# SparkFun_RTK_Express.net
KiCad netlist of a schematic drawn in EAGLE
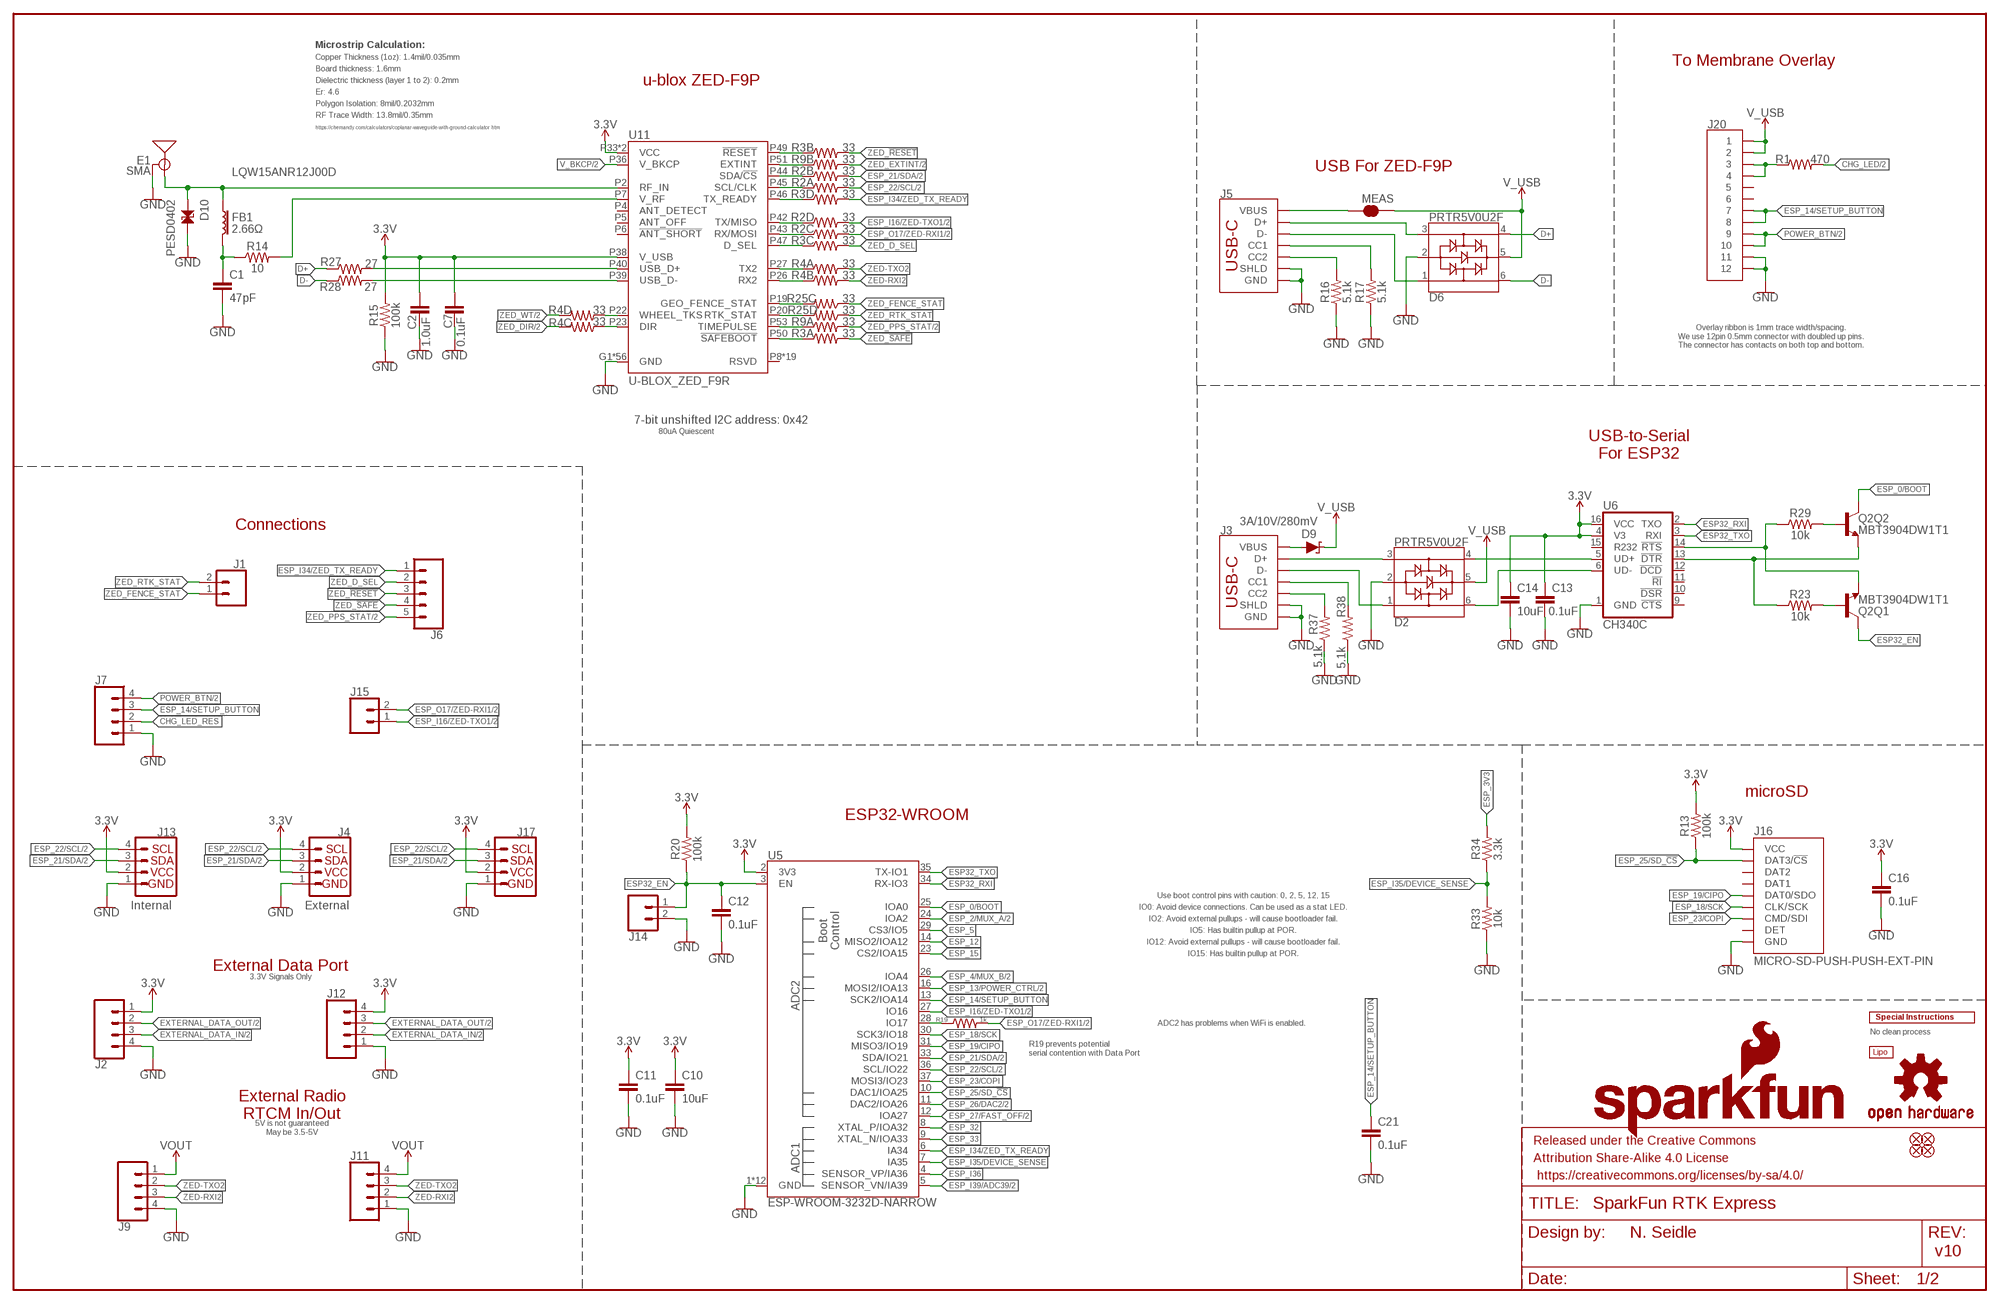
[diagram p0: schematic, sheet 1]
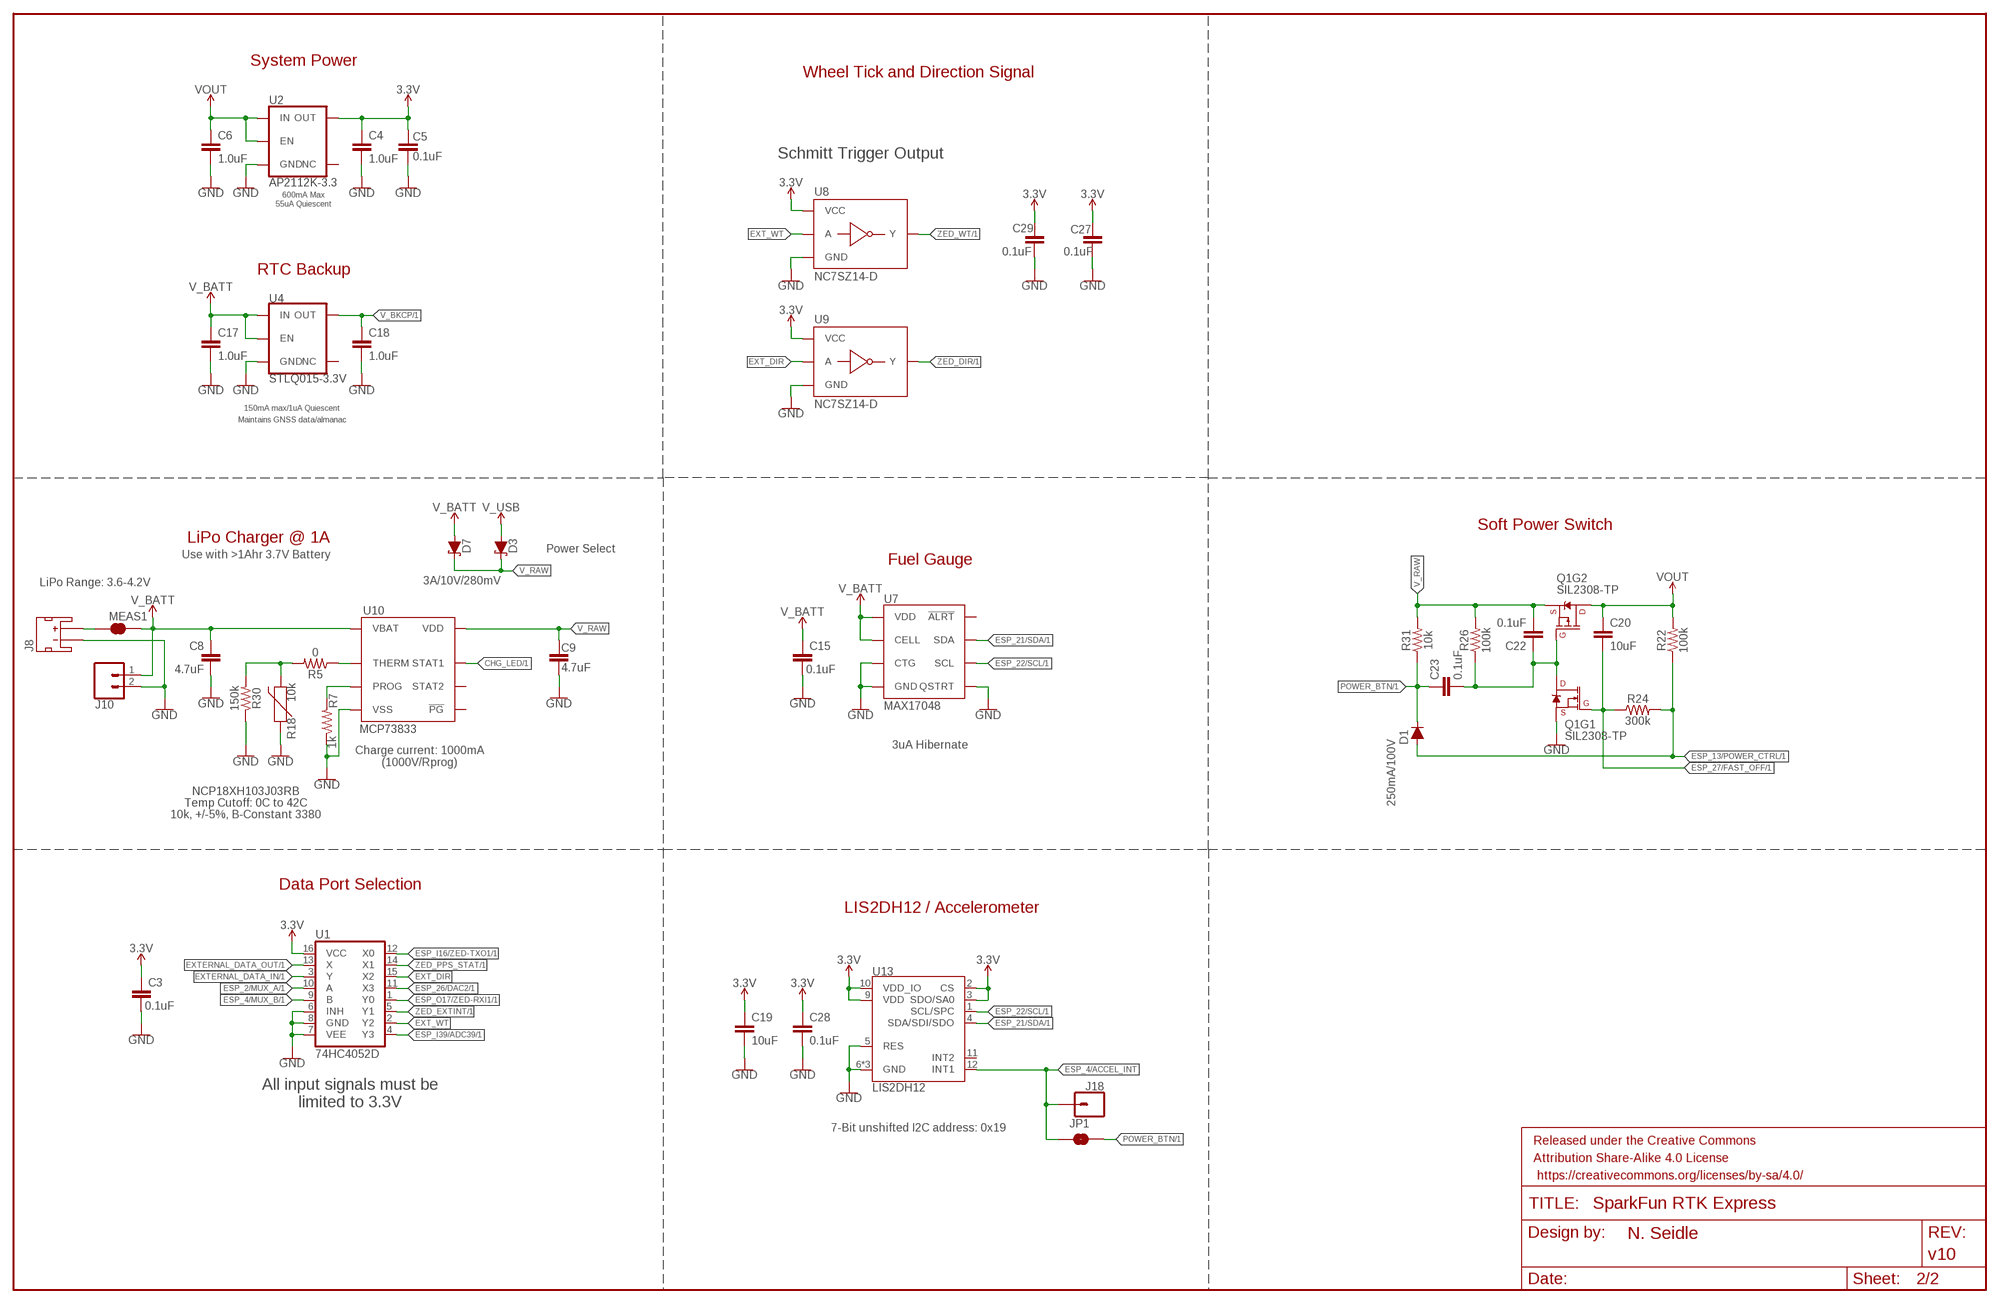
[diagram p1: schematic, sheet 2]

(export (version "E")
  (design (tool "Eeschema 10.0.6"))
  (components
    (comp (ref "C3")
      (value "0.1uF")
      (footprint "eagle-import:0603")
      (libsource (lib "eagle-import") (part "0.1UF-0603-25V-(+80/-20%)"))
    )
    (comp (ref "C4")
      (value "1.0uF")
      (footprint "eagle-import:0603")
      (libsource (lib "eagle-import") (part "1.0UF-0603-16V-10%-X7R"))
    )
    (comp (ref "C5")
      (value "0.1uF")
      (footprint "eagle-import:0603")
      (libsource (lib "eagle-import") (part "0.1UF-0603-25V-5%"))
    )
    (comp (ref "C6")
      (value "1.0uF")
      (footprint "eagle-import:0603")
      (libsource (lib "eagle-import") (part "1.0UF-0603-16V-10%-X7R"))
    )
    (comp (ref "C8")
      (value "4.7uF")
      (footprint "eagle-import:0603")
      (libsource (lib "eagle-import") (part "4.7UF-0603-35V-(20%)"))
    )
    (comp (ref "C9")
      (value "4.7uF")
      (footprint "eagle-import:0603")
      (libsource (lib "eagle-import") (part "4.7UF-0603-35V-(20%)"))
    )
    (comp (ref "C15")
      (value "0.1uF")
      (footprint "eagle-import:0603")
      (libsource (lib "eagle-import") (part "0.1UF-0603-25V-(+80/-20%)"))
    )
    (comp (ref "C17")
      (value "1.0uF")
      (footprint "eagle-import:0603")
      (libsource (lib "eagle-import") (part "1.0UF-0603-16V-10%-X7R"))
    )
    (comp (ref "C18")
      (value "1.0uF")
      (footprint "eagle-import:0603")
      (libsource (lib "eagle-import") (part "1.0UF-0603-16V-10%-X7R"))
    )
    (comp (ref "C19")
      (value "10uF")
      (footprint "eagle-import:0603")
      (libsource (lib "eagle-import") (part "10UF-0603-6.3V-20%"))
    )
    (comp (ref "C20")
      (value "10uF")
      (footprint "eagle-import:0603")
      (libsource (lib "eagle-import") (part "10UF-0603-6.3V-20%"))
    )
    (comp (ref "C22")
      (value "0.1uF")
      (footprint "eagle-import:0603")
      (libsource (lib "eagle-import") (part "0.1UF-0603-25V-5%"))
    )
    (comp (ref "C23")
      (value "0.1uF")
      (footprint "eagle-import:0603")
      (libsource (lib "eagle-import") (part "0.1UF-0603-25V-5%"))
    )
    (comp (ref "C27")
      (value "0.1uF")
      (footprint "eagle-import:0603")
      (libsource (lib "eagle-import") (part "0.1UF-0603-25V-(+80/-20%)"))
    )
    (comp (ref "C28")
      (value "0.1uF")
      (footprint "eagle-import:0603")
      (libsource (lib "eagle-import") (part "0.1UF-0603-25V-(+80/-20%)"))
    )
    (comp (ref "C29")
      (value "0.1uF")
      (footprint "eagle-import:0603")
      (libsource (lib "eagle-import") (part "0.1UF-0603-25V-(+80/-20%)"))
    )
    (comp (ref "D1")
      (value "250mA/100V")
      (footprint "eagle-import:SOD-323")
      (libsource (lib "eagle-import") (part "DIODE-BAS16J"))
    )
    (comp (ref "D3")
      (value "3A/10V/280mV")
      (footprint "eagle-import:SOD-323")
      (libsource (lib "eagle-import") (part "DIODE-SCHOTTKY-BAT60A"))
    )
    (comp (ref "D7")
      (value "3A/10V/280mV")
      (footprint "eagle-import:SOD-323")
      (libsource (lib "eagle-import") (part "DIODE-SCHOTTKY-BAT60A"))
    )
    (comp (ref "FRAME3")
      (value "FRAME-LEDGERNO_FOOTPRINT")
      (footprint "eagle-import:DUMMY")
      (fields (field (name "DESIGNER") "N. Seidle") (field (name "REV") "v10"))
      (libsource (lib "eagle-import") (part "FRAME-LEDGERNO_FOOTPRINT"))
    )
    (comp (ref "J8")
      (value "JST_2MM_MALE")
      (footprint "eagle-import:JST-2-SMD")
      (libsource (lib "eagle-import") (part "JST_2MM_MALE"))
    )
    (comp (ref "J10")
      (value "CONN_021X02_NO_SILK")
      (footprint "eagle-import:1X02_NO_SILK")
      (libsource (lib "eagle-import") (part "CONN_021X02_NO_SILK"))
    )
    (comp (ref "J18")
      (value "CONN_01PTH_NO_SILK_YES_STOP")
      (footprint "eagle-import:1X01_NO_SILK")
      (libsource (lib "eagle-import") (part "CONN_01PTH_NO_SILK_YES_STOP"))
    )
    (comp (ref "JP1")
      (value "JUMPER-SMT_2_NO_SILK")
      (footprint "eagle-import:SMT-JUMPER_2_NO_SILK")
      (libsource (lib "eagle-import") (part "JUMPER-SMT_2_NO_SILK"))
    )
    (comp (ref "MEAS1")
      (value "JUMPER-COMBO_2_NC_TRACE")
      (footprint "eagle-import:COMBO-JUMPER_2_NC_TRACE")
      (libsource (lib "eagle-import") (part "JUMPER-COMBO_2_NC_TRACE"))
    )
    (comp (ref "Q1")
      (value "SIL2308-TP")
      (footprint "eagle-import:SOT26")
      (libsource (lib "eagle-import") (part "MOSFET_COMPLIMENTARY_PAIR-SIL2308"))
    )
    (comp (ref "R5")
      (value "0")
      (footprint "eagle-import:0603")
      (libsource (lib "eagle-import") (part "0OHM-0603-1/10W"))
    )
    (comp (ref "R7")
      (value "1k")
      (footprint "eagle-import:0603")
      (libsource (lib "eagle-import") (part "1KOHM-0603-1/10W-1%"))
    )
    (comp (ref "R18")
      (value "10k")
      (footprint "eagle-import:0603")
      (libsource (lib "eagle-import") (part "NTC-THERMISTOR-0603"))
    )
    (comp (ref "R22")
      (value "100k")
      (footprint "eagle-import:0603")
      (libsource (lib "eagle-import") (part "100KOHM-0603-1/10W-1%"))
    )
    (comp (ref "R24")
      (value "300k")
      (footprint "eagle-import:0603")
      (libsource (lib "eagle-import") (part "300KOHM-0603-1/10W-1%"))
    )
    (comp (ref "R26")
      (value "100k")
      (footprint "eagle-import:0603")
      (libsource (lib "eagle-import") (part "100KOHM-0603-1/10W-1%"))
    )
    (comp (ref "R30")
      (value "150k")
      (footprint "eagle-import:0603")
      (libsource (lib "eagle-import") (part "150KOHM-0603-1/10W-1%"))
    )
    (comp (ref "R31")
      (value "10k")
      (footprint "eagle-import:0603")
      (libsource (lib "eagle-import") (part "10KOHM-0603-1/10W-1%"))
    )
    (comp (ref "U1")
      (value "74HC4052D")
      (footprint "eagle-import:SO16")
      (libsource (lib "eagle-import") (part "744052DHC"))
    )
    (comp (ref "U2")
      (value "AP2112K-3.3")
      (footprint "eagle-import:SOT23-5")
      (libsource (lib "eagle-import") (part "V_REG_AP2112K-3.3V"))
    )
    (comp (ref "U4")
      (value "STLQ015-3.3V")
      (footprint "eagle-import:SOT23-5")
      (libsource (lib "eagle-import") (part "STLQ015-3.3V"))
    )
    (comp (ref "U7")
      (value "MAX17048")
      (footprint "eagle-import:DFN-8")
      (libsource (lib "eagle-import") (part "MAX17048DFN8"))
    )
    (comp (ref "U8")
      (value "NC7SZ14-D")
      (footprint "eagle-import:SIP6")
      (libsource (lib "eagle-import") (part "UHS_INVERTER_SCHMITT_TRIGGERSIP6"))
    )
    (comp (ref "U9")
      (value "NC7SZ14-D")
      (footprint "eagle-import:SIP6")
      (libsource (lib "eagle-import") (part "UHS_INVERTER_SCHMITT_TRIGGERSIP6"))
    )
    (comp (ref "U10")
      (value "MCP73833")
      (footprint "eagle-import:DFN-10")
      (libsource (lib "eagle-import") (part "MCP73833"))
    )
    (comp (ref "U13")
      (value "LIS2DH12")
      (footprint "eagle-import:LGA-12-LISDH12")
      (libsource (lib "eagle-import") (part "LIS2DH12"))
    )
    (comp (ref "BT1")
      (value "LIPO-OUTLINE1000")
      (footprint "eagle-import:LIPO-1000")
      (libsource (lib "eagle-import") (part "LIPO-OUTLINE1000"))
    )
    (comp (ref "C1")
      (value "47pF")
      (footprint "eagle-import:0402")
      (libsource (lib "eagle-import") (part "47PF-0402-25V-5%-X7R"))
    )
    (comp (ref "C2")
      (value "1.0uF")
      (footprint "eagle-import:0603")
      (libsource (lib "eagle-import") (part "1.0UF-0603-16V-10%-X7R"))
    )
    (comp (ref "C7")
      (value "0.1uF")
      (footprint "eagle-import:0603")
      (libsource (lib "eagle-import") (part "0.1UF-0603-25V-5%"))
    )
    (comp (ref "C10")
      (value "10uF")
      (footprint "eagle-import:0603")
      (libsource (lib "eagle-import") (part "10UF-0603-6.3V-20%"))
    )
    (comp (ref "C11")
      (value "0.1uF")
      (footprint "eagle-import:0603")
      (libsource (lib "eagle-import") (part "0.1UF-0603-25V-(+80/-20%)"))
    )
    (comp (ref "C12")
      (value "0.1uF")
      (footprint "eagle-import:0603")
      (libsource (lib "eagle-import") (part "0.1UF-0603-25V-(+80/-20%)"))
    )
    (comp (ref "C13")
      (value "0.1uF")
      (footprint "eagle-import:0603")
      (libsource (lib "eagle-import") (part "0.1UF-0603-25V-(+80/-20%)"))
    )
    (comp (ref "C14")
      (value "10uF")
      (footprint "eagle-import:0603")
      (libsource (lib "eagle-import") (part "10UF-0603-6.3V-20%"))
    )
    (comp (ref "C16")
      (value "0.1uF")
      (footprint "eagle-import:0603")
      (libsource (lib "eagle-import") (part "0.1UF-0603-25V-(+80/-20%)"))
    )
    (comp (ref "C21")
      (value "0.1uF")
      (footprint "eagle-import:0603")
      (libsource (lib "eagle-import") (part "0.1UF-0603-25V-(+80/-20%)"))
    )
    (comp (ref "D2")
      (value "PRTR5V0U2F")
      (footprint "eagle-import:SOT886")
      (libsource (lib "eagle-import") (part "PRTR5V0U2F"))
    )
    (comp (ref "D6")
      (value "PRTR5V0U2F")
      (footprint "eagle-import:SOT886")
      (libsource (lib "eagle-import") (part "PRTR5V0U2F"))
    )
    (comp (ref "D9")
      (value "3A/10V/280mV")
      (footprint "eagle-import:SOD-323")
      (libsource (lib "eagle-import") (part "DIODE-SCHOTTKY-BAT60A"))
    )
    (comp (ref "D10")
      (value "PESD0402")
      (footprint "eagle-import:0402")
      (fields
        (field (name "DIGIKEY_PART") "PESD0402-140CT-ND")
        (field (name "MOUSE_PART") "650-PESD0402-140")
      )
      (libsource (lib "eagle-import") (part "PESD0402"))
    )
    (comp (ref "E1")
      (value "SMA")
      (footprint "eagle-import:SMA-EDGE")
      (libsource (lib "eagle-import") (part "ANTENNA-SMA-GROUNDEDEDGE_SMA"))
    )
    (comp (ref "FB1")
      (value "2.66Ω")
      (footprint "eagle-import:0402-TIGHT")
      (libsource (lib "eagle-import") (part "FERRITE_BEAD-0402-2.66Ω-1GHZ"))
    )
    (comp (ref "FRAME2")
      (value "FRAME-LEDGER")
      (footprint "eagle-import:CREATIVE_COMMONS")
      (libsource (lib "eagle-import") (part "FRAME-LEDGER"))
    )
    (comp (ref "J1")
      (value "CONN_021X02_NO_SILK")
      (footprint "eagle-import:1X02_NO_SILK")
      (libsource (lib "eagle-import") (part "CONN_021X02_NO_SILK"))
    )
    (comp (ref "J2")
      (value "CONN_04JST-SMD-LOCKING")
      (footprint "eagle-import:JST-4-SMD-1.25MM-LOCKING")
      (libsource (lib "eagle-import") (part "CONN_04JST-SMD-LOCKING"))
    )
    (comp (ref "J3")
      (value "USB Female Type C Connector")
      (footprint "eagle-import:USB-C-16P_4LAYER-PADS")
      (libsource (lib "eagle-import") (part "USB_C_4-LAYER_PADS"))
    )
    (comp (ref "J4")
      (value "External")
      (footprint "eagle-import:JST04_1MM_RA")
      (libsource (lib "eagle-import") (part "I2C_STANDARDQWIIC"))
    )
    (comp (ref "J5")
      (value "USB Female Type C Connector")
      (footprint "eagle-import:USB-C-16P_4LAYER-PADS")
      (libsource (lib "eagle-import") (part "USB_C_4-LAYER_PADS"))
    )
    (comp (ref "J6")
      (value "CONN_05NO_SILK")
      (footprint "eagle-import:1X05_NO_SILK")
      (libsource (lib "eagle-import") (part "CONN_05NO_SILK"))
    )
    (comp (ref "J7")
      (value "CONN_041X04_NO_SILK_NO_POP")
      (footprint "eagle-import:1X04_NO_SILK")
      (libsource (lib "eagle-import") (part "CONN_041X04_NO_SILK_NO_POP"))
    )
    (comp (ref "J9")
      (value "CONN_04JST-SMD-LOCKING")
      (footprint "eagle-import:JST-4-SMD-1.25MM-LOCKING")
      (libsource (lib "eagle-import") (part "CONN_04JST-SMD-LOCKING"))
    )
    (comp (ref "J11")
      (value "CONN_041X04_NO_SILK_NO_POP")
      (footprint "eagle-import:1X04_NO_SILK")
      (libsource (lib "eagle-import") (part "CONN_041X04_NO_SILK_NO_POP"))
    )
    (comp (ref "J12")
      (value "CONN_041X04_NO_SILK_NO_POP")
      (footprint "eagle-import:1X04_NO_SILK")
      (libsource (lib "eagle-import") (part "CONN_041X04_NO_SILK_NO_POP"))
    )
    (comp (ref "J13")
      (value "Internal")
      (footprint "eagle-import:JST04_1MM_RA")
      (libsource (lib "eagle-import") (part "I2C_STANDARDQWIIC"))
    )
    (comp (ref "J14")
      (value "CONN_021X02_NO_SILK")
      (footprint "eagle-import:1X02_NO_SILK")
      (libsource (lib "eagle-import") (part "CONN_021X02_NO_SILK"))
    )
    (comp (ref "J15")
      (value "CONN_021X02_NO_SILK")
      (footprint "eagle-import:1X02_NO_SILK")
      (libsource (lib "eagle-import") (part "CONN_021X02_NO_SILK"))
    )
    (comp (ref "J16")
      (value "MICRO-SD-PUSH-PUSH-EXT-PIN")
      (footprint "eagle-import:MICROSD-EXTERNALPIN")
      (libsource (lib "eagle-import") (part "MICRO-SD-PUSH-PUSH-EXT-PIN"))
    )
    (comp (ref "J17")
      (value "Qwiic Right Angle")
      (footprint "eagle-import:1X04_NO_SILK")
      (libsource (lib "eagle-import") (part "I2C_STANDARD_NO_SILK"))
    )
    (comp (ref "J20")
      (value "FPC_12_0.5MM_BACKFLIP")
      (footprint "eagle-import:FPC_12_DOUBLESIDED_BACKFLIP")
      (libsource (lib "eagle-import") (part "FPC_12_0.5MM_BACKFLIP"))
    )
    (comp (ref "JP21")
      (value "FIDUCIALUFIDUCIAL")
      (footprint "eagle-import:FIDUCIAL-MICRO")
      (libsource (lib "eagle-import") (part "FIDUCIALUFIDUCIAL"))
    )
    (comp (ref "JP61")
      (value "FIDUCIALUFIDUCIAL")
      (footprint "eagle-import:FIDUCIAL-MICRO")
      (libsource (lib "eagle-import") (part "FIDUCIALUFIDUCIAL"))
    )
    (comp (ref "JP71")
      (value "FIDUCIALUFIDUCIAL")
      (footprint "eagle-import:FIDUCIAL-MICRO")
      (libsource (lib "eagle-import") (part "FIDUCIALUFIDUCIAL"))
    )
    (comp (ref "JP81")
      (value "FIDUCIALUFIDUCIAL")
      (footprint "eagle-import:FIDUCIAL-MICRO")
      (libsource (lib "eagle-import") (part "FIDUCIALUFIDUCIAL"))
    )
    (comp (ref "LOGO1")
      (value "OSHW-LOGOMINI")
      (footprint "eagle-import:OSHW-LOGO-MINI")
      (libsource (lib "eagle-import") (part "OSHW-LOGOMINI"))
    )
    (comp (ref "LOGO2")
      (value "SFE_LOGO_NAME_FLAME.1_INCH")
      (footprint "eagle-import:SFE_LOGO_NAME_FLAME_.1")
      (libsource (lib "eagle-import") (part "SFE_LOGO_NAME_FLAME.1_INCH"))
    )
    (comp (ref "MEAS")
      (value "JUMPER-COMBO_2_NC_TRACE")
      (footprint "eagle-import:COMBO-JUMPER_2_NC_TRACE")
      (libsource (lib "eagle-import") (part "JUMPER-COMBO_2_NC_TRACE"))
    )
    (comp (ref "Q2")
      (value "MBT3904DW1T1")
      (footprint "eagle-import:SC70-6")
      (libsource (lib "eagle-import") (part "TRANS_NPN_DUAL-MBT3904DW1T1"))
    )
    (comp (ref "R1")
      (value "470")
      (footprint "eagle-import:0603")
      (libsource (lib "eagle-import") (part "470OHM-0603-1/10W-1%"))
    )
    (comp (ref "R2")
      (value "33")
      (footprint "eagle-import:1206_RA")
      (libsource (lib "eagle-import") (part "33OHM_RA-1206-1/16W-5%"))
    )
    (comp (ref "R3")
      (value "33")
      (footprint "eagle-import:1206_RA")
      (libsource (lib "eagle-import") (part "33OHM_RA-1206-1/16W-5%"))
    )
    (comp (ref "R4")
      (value "33")
      (footprint "eagle-import:1206_RA")
      (libsource (lib "eagle-import") (part "33OHM_RA-1206-1/16W-5%"))
    )
    (comp (ref "R9")
      (value "33")
      (footprint "eagle-import:1206_RA")
      (libsource (lib "eagle-import") (part "33OHM_RA-1206-1/16W-5%"))
    )
    (comp (ref "R13")
      (value "100k")
      (footprint "eagle-import:0603")
      (libsource (lib "eagle-import") (part "100KOHM-0603-1/10W-1%"))
    )
    (comp (ref "R14")
      (value "10")
      (footprint "eagle-import:0603")
      (libsource (lib "eagle-import") (part "10OHM-0603-1/10W-1%"))
    )
    (comp (ref "R15")
      (value "100k")
      (footprint "eagle-import:0603")
      (libsource (lib "eagle-import") (part "100KOHM-0603-1/10W-1%"))
    )
    (comp (ref "R16")
      (value "5.1k")
      (footprint "eagle-import:0603")
      (libsource (lib "eagle-import") (part "5.1KOHM5.1KOHM-0603-1/10W-1%"))
    )
    (comp (ref "R17")
      (value "5.1k")
      (footprint "eagle-import:0603")
      (libsource (lib "eagle-import") (part "5.1KOHM5.1KOHM-0603-1/10W-1%"))
    )
    (comp (ref "R19")
      (value "1k")
      (footprint "eagle-import:0603")
      (libsource (lib "eagle-import") (part "1KOHM-0603-1/10W-1%"))
    )
    (comp (ref "R20")
      (value "100k")
      (footprint "eagle-import:0603")
      (libsource (lib "eagle-import") (part "100KOHM-0603-1/10W-1%"))
    )
    (comp (ref "R23")
      (value "10k")
      (footprint "eagle-import:0603")
      (libsource (lib "eagle-import") (part "10KOHM-0603-1/10W-1%"))
    )
    (comp (ref "R25")
      (value "33")
      (footprint "eagle-import:1206_RA")
      (libsource (lib "eagle-import") (part "33OHM_RA-1206-1/16W-5%"))
    )
    (comp (ref "R27")
      (value "27")
      (footprint "eagle-import:0603")
      (libsource (lib "eagle-import") (part "27OHM-0603-1/10W-1%"))
    )
    (comp (ref "R28")
      (value "27")
      (footprint "eagle-import:0603")
      (libsource (lib "eagle-import") (part "27OHM-0603-1/10W-1%"))
    )
    (comp (ref "R29")
      (value "10k")
      (footprint "eagle-import:0603")
      (libsource (lib "eagle-import") (part "10KOHM-0603-1/10W-1%"))
    )
    (comp (ref "R33")
      (value "10k")
      (footprint "eagle-import:0603")
      (libsource (lib "eagle-import") (part "10KOHM-0603-1/10W-1%"))
    )
    (comp (ref "R34")
      (value "3.3k")
      (footprint "eagle-import:0603")
      (libsource (lib "eagle-import") (part "3.3KOHM-0603-1/10W-1%"))
    )
    (comp (ref "R37")
      (value "5.1k")
      (footprint "eagle-import:0603")
      (libsource (lib "eagle-import") (part "5.1KOHM5.1KOHM-0603-1/10W-1%"))
    )
    (comp (ref "R38")
      (value "5.1k")
      (footprint "eagle-import:0603")
      (libsource (lib "eagle-import") (part "5.1KOHM5.1KOHM-0603-1/10W-1%"))
    )
    (comp (ref "U$2")
      (value "SPECIAL_INSTRUCTIONS-ORDERING")
      (footprint "eagle-import:ORDERING_INSTRUCTIONS")
      (libsource (lib "eagle-import") (part "SPECIAL_INSTRUCTIONS-ORDERING"))
    )
    (comp (ref "U5")
      (value "ESP-WROOM-3232D-NARROW")
      (footprint "eagle-import:ESP-WROOM-32D-NARROW")
      (libsource (lib "eagle-import") (part "ESP-WROOM-3232D-NARROW"))
    )
    (comp (ref "U6")
      (value "CH340C")
      (footprint "eagle-import:SO016")
      (libsource (lib "eagle-import") (part "CH340C"))
    )
    (comp (ref "U11")
      (value "U-BLOX_ZED_F9R")
      (footprint "eagle-import:UBLOX_ZED_F9R")
      (libsource (lib "eagle-import") (part "U-BLOX_ZED_F9R"))
    )
  )
  (nets
    (net (code "1") (name "3.3V") (class "Default")
      (node (ref "C10") (pin "1") (pinfunction "1_1") (pintype "passive"))
      (node (ref "C11") (pin "1") (pinfunction "1_1") (pintype "passive"))
      (node (ref "C13") (pin "1") (pinfunction "1_1") (pintype "passive"))
      (node (ref "C14") (pin "1") (pinfunction "1_1") (pintype "passive"))
      (node (ref "C16") (pin "1") (pinfunction "1_1") (pintype "passive"))
      (node (ref "C19") (pin "1") (pinfunction "1_1") (pintype "passive"))
      (node (ref "C2") (pin "1") (pinfunction "1_1") (pintype "passive"))
      (node (ref "C27") (pin "1") (pinfunction "1_1") (pintype "passive"))
      (node (ref "C28") (pin "1") (pinfunction "1_1") (pintype "passive"))
      (node (ref "C29") (pin "1") (pinfunction "1_1") (pintype "passive"))
      (node (ref "C3") (pin "1") (pinfunction "1_1") (pintype "passive"))
      (node (ref "C4") (pin "1") (pinfunction "1_1") (pintype "passive"))
      (node (ref "C5") (pin "2") (pinfunction "2_2") (pintype "passive"))
      (node (ref "C7") (pin "2") (pinfunction "2_2") (pintype "passive"))
      (node (ref "J12") (pin "4") (pinfunction "4_4") (pintype "passive"))
      (node (ref "J13") (pin "2") (pinfunction "2_2") (pintype "power_in"))
      (node (ref "J16") (pin "4") (pinfunction "VCC_4") (pintype "bidirectional"))
      (node (ref "J17") (pin "2") (pinfunction "2_2") (pintype "power_in"))
      (node (ref "J2") (pin "1") (pinfunction "1_1") (pintype "passive"))
      (node (ref "J4") (pin "2") (pinfunction "2_2") (pintype "power_in"))
      (node (ref "R13") (pin "2") (pinfunction "2_2") (pintype "passive"))
      (node (ref "R15") (pin "2") (pinfunction "2_2") (pintype "passive"))
      (node (ref "R20") (pin "2") (pinfunction "2_2") (pintype "passive"))
      (node (ref "U1") (pin "16") (pinfunction "VCC_16") (pintype "power_in"))
      (node (ref "U11") (pin "P33") (pinfunction "VCC_P33") (pintype "power_in"))
      (node (ref "U11") (pin "P34") (pinfunction "VCC_P34") (pintype "power_in"))
      (node (ref "U11") (pin "P38") (pinfunction "V_USB_P38") (pintype "power_in"))
      (node (ref "U13") (pin "10") (pinfunction "VDD_IO_10") (pintype "bidirectional"))
      (node (ref "U13") (pin "2") (pinfunction "CS_2") (pintype "bidirectional"))
      (node (ref "U13") (pin "3") (pinfunction "SDO/SA0_3") (pintype "bidirectional"))
      (node (ref "U13") (pin "9") (pinfunction "VDD_9") (pintype "bidirectional"))
      (node (ref "U2") (pin "5") (pinfunction "OUT_5") (pintype "passive"))
      (node (ref "U5") (pin "2") (pinfunction "3V3_2") (pintype "bidirectional"))
      (node (ref "U6") (pin "16") (pinfunction "VCC_16") (pintype "bidirectional"))
      (node (ref "U6") (pin "4") (pinfunction "V3_4") (pintype "bidirectional"))
      (node (ref "U8") (pin "P6") (pinfunction "VCC_P6") (pintype "power_in"))
      (node (ref "U9") (pin "P6") (pinfunction "VCC_P6") (pintype "power_in"))
    )
    (net (code "2") (name "CHG_LED") (class "Default")
      (node (ref "R1") (pin "2") (pinfunction "2_2") (pintype "passive"))
      (node (ref "U10") (pin "3") (pinfunction "STAT1_3") (pintype "bidirectional"))
    )
    (net (code "3") (name "CHG_LED_RES") (class "Default")
      (node (ref "J20") (pin "3") (pinfunction "3_3") (pintype "bidirectional"))
      (node (ref "J20") (pin "4") (pinfunction "4_4") (pintype "bidirectional"))
      (node (ref "J7") (pin "2") (pinfunction "2_2") (pintype "passive"))
      (node (ref "R1") (pin "1") (pinfunction "1_1") (pintype "passive"))
    )
    (net (code "4") (name "D+") (class "Default")
      (node (ref "D6") (pin "4") (pinfunction "4_4") (pintype "bidirectional"))
      (node (ref "R27") (pin "1") (pinfunction "1_1") (pintype "passive"))
    )
    (net (code "5") (name "D-") (class "Default")
      (node (ref "D6") (pin "6") (pinfunction "6_6") (pintype "bidirectional"))
      (node (ref "R28") (pin "1") (pinfunction "1_1") (pintype "passive"))
    )
    (net (code "6") (name "ESP32_EN") (class "Default")
      (node (ref "C12") (pin "1") (pinfunction "1_1") (pintype "passive"))
      (node (ref "J14") (pin "1") (pinfunction "1_1") (pintype "passive"))
      (node (ref "Q2") (pin "3") (pinfunction "C_3") (pintype "passive"))
      (node (ref "R20") (pin "1") (pinfunction "1_1") (pintype "passive"))
      (node (ref "U5") (pin "3") (pinfunction "EN_3") (pintype "bidirectional"))
    )
    (net (code "7") (name "ESP32_RXI") (class "Default")
      (node (ref "U5") (pin "34") (pinfunction "RX-IO3_34") (pintype "bidirectional"))
      (node (ref "U6") (pin "2") (pinfunction "TXO_2") (pintype "bidirectional"))
    )
    (net (code "8") (name "ESP32_TXO") (class "Default")
      (node (ref "U5") (pin "35") (pinfunction "TX-IO1_35") (pintype "bidirectional"))
      (node (ref "U6") (pin "3") (pinfunction "RXI_3") (pintype "bidirectional"))
    )
    (net (code "9") (name "ESP_0{slash}BOOT") (class "Default")
      (node (ref "Q2") (pin "6") (pinfunction "C_6") (pintype "passive"))
      (node (ref "U5") (pin "25") (pinfunction "IOA0_25") (pintype "bidirectional"))
    )
    (net (code "10") (name "ESP_2{slash}MUX_A") (class "Default")
      (node (ref "U1") (pin "10") (pinfunction "A_10") (pintype "input"))
      (node (ref "U5") (pin "24") (pinfunction "IOA2_24") (pintype "bidirectional"))
    )
    (net (code "11") (name "ESP_3V3") (class "Default")
      (node (ref "R34") (pin "2") (pinfunction "2_2") (pintype "passive"))
    )
    (net (code "12") (name "ESP_4{slash}ACCEL_INT") (class "Default")
      (node (ref "J18") (pin "1") (pinfunction "1_1") (pintype "passive"))
      (node (ref "JP1") (pin "1") (pinfunction "1_1") (pintype "passive"))
      (node (ref "U13") (pin "12") (pinfunction "INT1_12") (pintype "bidirectional"))
    )
    (net (code "13") (name "ESP_4{slash}MUX_B") (class "Default")
      (node (ref "U1") (pin "9") (pinfunction "B_9") (pintype "input"))
      (node (ref "U5") (pin "26") (pinfunction "IOA4_26") (pintype "bidirectional"))
    )
    (net (code "14") (name "ESP_5") (class "Default")
      (node (ref "U5") (pin "29") (pinfunction "CS3/IO5_29") (pintype "bidirectional"))
    )
    (net (code "15") (name "ESP_12") (class "Default")
      (node (ref "U5") (pin "14") (pinfunction "MISO2/IOA12_14") (pintype "bidirectional"))
    )
    (net (code "16") (name "ESP_13{slash}POWER_CTRL") (class "Default")
      (node (ref "D1") (pin "A") (pinfunction "A_A") (pintype "passive"))
      (node (ref "R22") (pin "1") (pinfunction "1_1") (pintype "passive"))
      (node (ref "R24") (pin "2") (pinfunction "2_2") (pintype "passive"))
      (node (ref "U5") (pin "16") (pinfunction "MOSI2/IOA13_16") (pintype "bidirectional"))
    )
    (net (code "17") (name "ESP_14{slash}SETUP_BUTTON") (class "Default")
      (node (ref "C21") (pin "1") (pinfunction "1_1") (pintype "passive"))
      (node (ref "J20") (pin "7") (pinfunction "7_7") (pintype "bidirectional"))
      (node (ref "J20") (pin "8") (pinfunction "8_8") (pintype "bidirectional"))
      (node (ref "J7") (pin "3") (pinfunction "3_3") (pintype "passive"))
      (node (ref "U5") (pin "13") (pinfunction "SCK2/IOA14_13") (pintype "bidirectional"))
    )
    (net (code "18") (name "ESP_15") (class "Default")
      (node (ref "U5") (pin "23") (pinfunction "CS2/IOA15_23") (pintype "bidirectional"))
    )
    (net (code "19") (name "ESP_18{slash}SCK") (class "Default")
      (node (ref "J16") (pin "5") (pinfunction "CLK/SCK_5") (pintype "bidirectional"))
      (node (ref "U5") (pin "30") (pinfunction "SCK3/IO18_30") (pintype "bidirectional"))
    )
    (net (code "20") (name "ESP_19{slash}CIPO") (class "Default")
      (node (ref "J16") (pin "7") (pinfunction "DAT0/SDO_7") (pintype "bidirectional"))
      (node (ref "U5") (pin "31") (pinfunction "MISO3/IO19_31") (pintype "bidirectional"))
    )
    (net (code "21") (name "ESP_21{slash}SDA") (class "Default")
      (node (ref "J13") (pin "3") (pinfunction "3_3") (pintype "passive"))
      (node (ref "J17") (pin "3") (pinfunction "3_3") (pintype "passive"))
      (node (ref "J4") (pin "3") (pinfunction "3_3") (pintype "passive"))
      (node (ref "R2") (pin "P7") (pinfunction "2_P7") (pintype "passive"))
      (node (ref "U13") (pin "4") (pinfunction "SDA/SDI/SDO_4") (pintype "bidirectional"))
      (node (ref "U5") (pin "33") (pinfunction "SDA/IO21_33") (pintype "bidirectional"))
      (node (ref "U7") (pin "8") (pinfunction "SDA_8") (pintype "input"))
    )
    (net (code "22") (name "ESP_22{slash}SCL") (class "Default")
      (node (ref "J13") (pin "4") (pinfunction "4_4") (pintype "passive"))
      (node (ref "J17") (pin "4") (pinfunction "4_4") (pintype "passive"))
      (node (ref "J4") (pin "4") (pinfunction "4_4") (pintype "passive"))
      (node (ref "R2") (pin "P8") (pinfunction "2_P8") (pintype "passive"))
      (node (ref "U13") (pin "1") (pinfunction "SCL/SPC_1") (pintype "bidirectional"))
      (node (ref "U5") (pin "36") (pinfunction "SCL/IO22_36") (pintype "bidirectional"))
      (node (ref "U7") (pin "7") (pinfunction "SCL_7") (pintype "output"))
    )
    (net (code "23") (name "ESP_23{slash}COPI") (class "Default")
      (node (ref "J16") (pin "3") (pinfunction "CMD/SDI_3") (pintype "bidirectional"))
      (node (ref "U5") (pin "37") (pinfunction "MOSI3/IO23_37") (pintype "bidirectional"))
    )
    (net (code "24") (name "ESP_25{slash}SD_~{CS}") (class "Default")
      (node (ref "J16") (pin "2") (pinfunction "DAT3/~{CS}_2") (pintype "bidirectional"))
      (node (ref "R13") (pin "1") (pinfunction "1_1") (pintype "passive"))
      (node (ref "U5") (pin "10") (pinfunction "DAC1/IOA25_10") (pintype "bidirectional"))
    )
    (net (code "25") (name "ESP_26{slash}DAC2") (class "Default")
      (node (ref "U1") (pin "11") (pinfunction "X3_11") (pintype "bidirectional"))
      (node (ref "U5") (pin "11") (pinfunction "DAC2/IOA26_11") (pintype "bidirectional"))
    )
    (net (code "26") (name "ESP_27{slash}FAST_OFF") (class "Default")
      (node (ref "C20") (pin "2") (pinfunction "2_2") (pintype "passive"))
      (node (ref "Q1") (pin "G1") (pinfunction "G_G1") (pintype "bidirectional"))
      (node (ref "R24") (pin "1") (pinfunction "1_1") (pintype "passive"))
      (node (ref "U5") (pin "12") (pinfunction "IOA27_12") (pintype "bidirectional"))
    )
    (net (code "27") (name "ESP_32") (class "Default")
      (node (ref "U5") (pin "8") (pinfunction "XTAL_P/IOA32_8") (pintype "bidirectional"))
    )
    (net (code "28") (name "ESP_33") (class "Default")
      (node (ref "U5") (pin "9") (pinfunction "XTAL_N/IOA33_9") (pintype "bidirectional"))
    )
    (net (code "29") (name "ESP_I16{slash}ZED-TXO1") (class "Default")
      (node (ref "J15") (pin "1") (pinfunction "1_1") (pintype "passive"))
      (node (ref "R2") (pin "P5") (pinfunction "2_P5") (pintype "passive"))
      (node (ref "U1") (pin "12") (pinfunction "X0_12") (pintype "bidirectional"))
      (node (ref "U5") (pin "27") (pinfunction "IO16_27") (pintype "bidirectional"))
    )
    (net (code "30") (name "ESP_I34{slash}ZED_TX_READY") (class "Default")
      (node (ref "J6") (pin "1") (pinfunction "1_1") (pintype "passive"))
      (node (ref "R3") (pin "P5") (pinfunction "2_P5") (pintype "passive"))
      (node (ref "U5") (pin "6") (pinfunction "IA34_6") (pintype "bidirectional"))
    )
    (net (code "31") (name "ESP_I35{slash}DEVICE_SENSE") (class "Default")
      (node (ref "R33") (pin "2") (pinfunction "2_2") (pintype "passive"))
      (node (ref "R34") (pin "1") (pinfunction "1_1") (pintype "passive"))
      (node (ref "U5") (pin "7") (pinfunction "IA35_7") (pintype "bidirectional"))
    )
    (net (code "32") (name "ESP_I36") (class "Default")
      (node (ref "U5") (pin "4") (pinfunction "SENSOR_VP/IA36_4") (pintype "bidirectional"))
    )
    (net (code "33") (name "ESP_I39{slash}ADC39") (class "Default")
      (node (ref "U1") (pin "4") (pinfunction "Y3_4") (pintype "bidirectional"))
      (node (ref "U5") (pin "5") (pinfunction "SENSOR_VN/IA39_5") (pintype "bidirectional"))
    )
    (net (code "34") (name "ESP_O17{slash}ZED-RXI1") (class "Default")
      (node (ref "J15") (pin "2") (pinfunction "2_2") (pintype "passive"))
      (node (ref "R19") (pin "2") (pinfunction "2_2") (pintype "passive"))
      (node (ref "R2") (pin "P6") (pinfunction "2_P6") (pintype "passive"))
      (node (ref "U1") (pin "1") (pinfunction "Y0_1") (pintype "bidirectional"))
    )
    (net (code "35") (name "EXTERNAL_DATA_IN") (class "Default")
      (node (ref "J12") (pin "2") (pinfunction "2_2") (pintype "passive"))
      (node (ref "J2") (pin "3") (pinfunction "3_3") (pintype "passive"))
      (node (ref "U1") (pin "3") (pinfunction "Y_3") (pintype "bidirectional"))
    )
    (net (code "36") (name "EXTERNAL_DATA_OUT") (class "Default")
      (node (ref "J12") (pin "3") (pinfunction "3_3") (pintype "passive"))
      (node (ref "J2") (pin "2") (pinfunction "2_2") (pintype "passive"))
      (node (ref "U1") (pin "13") (pinfunction "X_13") (pintype "bidirectional"))
    )
    (net (code "37") (name "EXT_DIR") (class "Default")
      (node (ref "U1") (pin "15") (pinfunction "X2_15") (pintype "bidirectional"))
      (node (ref "U9") (pin "P2") (pinfunction "A_P2") (pintype "input"))
    )
    (net (code "38") (name "EXT_WT") (class "Default")
      (node (ref "U1") (pin "2") (pinfunction "Y2_2") (pintype "bidirectional"))
      (node (ref "U8") (pin "P2") (pinfunction "A_P2") (pintype "input"))
    )
    (net (code "39") (name "GND") (class "Default")
      (node (ref "C1") (pin "2") (pinfunction "2_2") (pintype "passive"))
      (node (ref "C10") (pin "2") (pinfunction "2_2") (pintype "passive"))
      (node (ref "C11") (pin "2") (pinfunction "2_2") (pintype "passive"))
      (node (ref "C12") (pin "2") (pinfunction "2_2") (pintype "passive"))
      (node (ref "C13") (pin "2") (pinfunction "2_2") (pintype "passive"))
      (node (ref "C14") (pin "2") (pinfunction "2_2") (pintype "passive"))
      (node (ref "C15") (pin "2") (pinfunction "2_2") (pintype "passive"))
      (node (ref "C16") (pin "2") (pinfunction "2_2") (pintype "passive"))
      (node (ref "C17") (pin "2") (pinfunction "2_2") (pintype "passive"))
      (node (ref "C18") (pin "2") (pinfunction "2_2") (pintype "passive"))
      (node (ref "C19") (pin "2") (pinfunction "2_2") (pintype "passive"))
      (node (ref "C2") (pin "2") (pinfunction "2_2") (pintype "passive"))
      (node (ref "C21") (pin "2") (pinfunction "2_2") (pintype "passive"))
      (node (ref "C27") (pin "2") (pinfunction "2_2") (pintype "passive"))
      (node (ref "C28") (pin "2") (pinfunction "2_2") (pintype "passive"))
      (node (ref "C29") (pin "2") (pinfunction "2_2") (pintype "passive"))
      (node (ref "C3") (pin "2") (pinfunction "2_2") (pintype "passive"))
      (node (ref "C4") (pin "2") (pinfunction "2_2") (pintype "passive"))
      (node (ref "C5") (pin "1") (pinfunction "1_1") (pintype "passive"))
      (node (ref "C6") (pin "2") (pinfunction "2_2") (pintype "passive"))
      (node (ref "C7") (pin "1") (pinfunction "1_1") (pintype "passive"))
      (node (ref "C8") (pin "2") (pinfunction "2_2") (pintype "passive"))
      (node (ref "C9") (pin "2") (pinfunction "2_2") (pintype "passive"))
      (node (ref "D10") (pin "2") (pinfunction "2_2") (pintype "bidirectional"))
      (node (ref "D2") (pin "2") (pinfunction "2_2") (pintype "power_in"))
      (node (ref "D6") (pin "2") (pinfunction "2_2") (pintype "power_in"))
      (node (ref "E1") (pin "GND@0") (pinfunction "GND_GND@0") (pintype "bidirectional"))
      (node (ref "E1") (pin "GND@1") (pinfunction "GND_GND@1") (pintype "bidirectional"))
      (node (ref "E1") (pin "GND@2") (pinfunction "GND_GND@2") (pintype "bidirectional"))
      (node (ref "E1") (pin "GND@3") (pinfunction "GND_GND@3") (pintype "bidirectional"))
      (node (ref "J10") (pin "2") (pinfunction "2_2") (pintype "passive"))
      (node (ref "J11") (pin "1") (pinfunction "1_1") (pintype "passive"))
      (node (ref "J12") (pin "1") (pinfunction "1_1") (pintype "passive"))
      (node (ref "J13") (pin "1") (pinfunction "1_1") (pintype "power_in"))
      (node (ref "J14") (pin "2") (pinfunction "2_2") (pintype "passive"))
      (node (ref "J16") (pin "10") (pinfunction "GND_10") (pintype "bidirectional"))
      (node (ref "J16") (pin "11") (pinfunction "GND_11") (pintype "bidirectional"))
      (node (ref "J16") (pin "12") (pinfunction "GND_12") (pintype "bidirectional"))
      (node (ref "J16") (pin "13") (pinfunction "GND_13") (pintype "bidirectional"))
      (node (ref "J16") (pin "6") (pinfunction "GND_6") (pintype "bidirectional"))
      (node (ref "J17") (pin "1") (pinfunction "1_1") (pintype "power_in"))
      (node (ref "J2") (pin "4") (pinfunction "4_4") (pintype "passive"))
      (node (ref "J20") (pin "11") (pinfunction "11_11") (pintype "bidirectional"))
      (node (ref "J20") (pin "12") (pinfunction "12_12") (pintype "bidirectional"))
      (node (ref "J3") (pin "GND") (pinfunction "GND_GND") (pintype "bidirectional"))
      (node (ref "J3") (pin "GND2") (pinfunction "GND_GND2") (pintype "bidirectional"))
      (node (ref "J3") (pin "SHLD1") (pinfunction "SHLD_SHLD1") (pintype "bidirectional"))
      (node (ref "J3") (pin "SHLD2") (pinfunction "SHLD_SHLD2") (pintype "bidirectional"))
      (node (ref "J3") (pin "SHLD3") (pinfunction "SHLD_SHLD3") (pintype "bidirectional"))
      (node (ref "J3") (pin "SHLD4") (pinfunction "SHLD_SHLD4") (pintype "bidirectional"))
      (node (ref "J4") (pin "1") (pinfunction "1_1") (pintype "power_in"))
      (node (ref "J5") (pin "GND") (pinfunction "GND_GND") (pintype "bidirectional"))
      (node (ref "J5") (pin "GND2") (pinfunction "GND_GND2") (pintype "bidirectional"))
      (node (ref "J5") (pin "SHLD1") (pinfunction "SHLD_SHLD1") (pintype "bidirectional"))
      (node (ref "J5") (pin "SHLD2") (pinfunction "SHLD_SHLD2") (pintype "bidirectional"))
      (node (ref "J5") (pin "SHLD3") (pinfunction "SHLD_SHLD3") (pintype "bidirectional"))
      (node (ref "J5") (pin "SHLD4") (pinfunction "SHLD_SHLD4") (pintype "bidirectional"))
      (node (ref "J7") (pin "1") (pinfunction "1_1") (pintype "passive"))
      (node (ref "J8") (pin "1") (pinfunction "-_1") (pintype "bidirectional"))
      (node (ref "J9") (pin "4") (pinfunction "4_4") (pintype "passive"))
      (node (ref "Q1") (pin "S1") (pinfunction "S_S1") (pintype "bidirectional"))
      (node (ref "R15") (pin "1") (pinfunction "1_1") (pintype "passive"))
      (node (ref "R16") (pin "1") (pinfunction "1_1") (pintype "passive"))
      (node (ref "R17") (pin "1") (pinfunction "1_1") (pintype "passive"))
      (node (ref "R18") (pin "1") (pinfunction "1_1") (pintype "bidirectional"))
      (node (ref "R30") (pin "1") (pinfunction "1_1") (pintype "passive"))
      (node (ref "R33") (pin "1") (pinfunction "1_1") (pintype "passive"))
      (node (ref "R37") (pin "1") (pinfunction "1_1") (pintype "passive"))
      (node (ref "R38") (pin "1") (pinfunction "1_1") (pintype "passive"))
      (node (ref "R7") (pin "1") (pinfunction "1_1") (pintype "passive"))
      (node (ref "U1") (pin "6") (pinfunction "INH_6") (pintype "input"))
      (node (ref "U1") (pin "7") (pinfunction "VEE_7") (pintype "power_in"))
      (node (ref "U1") (pin "8") (pinfunction "GND_8") (pintype "power_in"))
      (node (ref "U10") (pin "11") (pinfunction "VSS_11") (pintype "bidirectional"))
      (node (ref "U10") (pin "5") (pinfunction "VSS_5") (pintype "bidirectional"))
      (node (ref "U11") (pin "G1") (pinfunction "GND_G1") (pintype "power_in"))
      (node (ref "U11") (pin "G10") (pinfunction "GND_G10") (pintype "power_in"))
      (node (ref "U11") (pin "G11") (pinfunction "GND_G11") (pintype "power_in"))
      (node (ref "U11") (pin "G12") (pinfunction "GND_G12") (pintype "power_in"))
      (node (ref "U11") (pin "G13") (pinfunction "GND_G13") (pintype "power_in"))
      (node (ref "U11") (pin "G14") (pinfunction "GND_G14") (pintype "power_in"))
      (node (ref "U11") (pin "G15") (pinfunction "GND_G15") (pintype "power_in"))
      (node (ref "U11") (pin "G16") (pinfunction "GND_G16") (pintype "power_in"))
      (node (ref "U11") (pin "G17") (pinfunction "GND_G17") (pintype "power_in"))
      (node (ref "U11") (pin "G18") (pinfunction "GND_G18") (pintype "power_in"))
      (node (ref "U11") (pin "G19") (pinfunction "GND_G19") (pintype "power_in"))
      (node (ref "U11") (pin "G2") (pinfunction "GND_G2") (pintype "power_in"))
      (node (ref "U11") (pin "G20") (pinfunction "GND_G20") (pintype "power_in"))
      (node (ref "U11") (pin "G21") (pinfunction "GND_G21") (pintype "power_in"))
      (node (ref "U11") (pin "G22") (pinfunction "GND_G22") (pintype "power_in"))
      (node (ref "U11") (pin "G23") (pinfunction "GND_G23") (pintype "power_in"))
      (node (ref "U11") (pin "G24") (pinfunction "GND_G24") (pintype "power_in"))
      (node (ref "U11") (pin "G25") (pinfunction "GND_G25") (pintype "power_in"))
      (node (ref "U11") (pin "G26") (pinfunction "GND_G26") (pintype "power_in"))
      (node (ref "U11") (pin "G27") (pinfunction "GND_G27") (pintype "power_in"))
      (node (ref "U11") (pin "G28") (pinfunction "GND_G28") (pintype "power_in"))
      (node (ref "U11") (pin "G29") (pinfunction "GND_G29") (pintype "power_in"))
      (node (ref "U11") (pin "G3") (pinfunction "GND_G3") (pintype "power_in"))
      (node (ref "U11") (pin "G30") (pinfunction "GND_G30") (pintype "power_in"))
      (node (ref "U11") (pin "G31") (pinfunction "GND_G31") (pintype "power_in"))
      (node (ref "U11") (pin "G32") (pinfunction "GND_G32") (pintype "power_in"))
      (node (ref "U11") (pin "G33") (pinfunction "GND_G33") (pintype "power_in"))
      (node (ref "U11") (pin "G34") (pinfunction "GND_G34") (pintype "power_in"))
      (node (ref "U11") (pin "G35") (pinfunction "GND_G35") (pintype "power_in"))
      (node (ref "U11") (pin "G36") (pinfunction "GND_G36") (pintype "power_in"))
      (node (ref "U11") (pin "G37") (pinfunction "GND_G37") (pintype "power_in"))
      (node (ref "U11") (pin "G38") (pinfunction "GND_G38") (pintype "power_in"))
      (node (ref "U11") (pin "G39") (pinfunction "GND_G39") (pintype "power_in"))
      (node (ref "U11") (pin "G4") (pinfunction "GND_G4") (pintype "power_in"))
      (node (ref "U11") (pin "G40") (pinfunction "GND_G40") (pintype "power_in"))
      (node (ref "U11") (pin "G41") (pinfunction "GND_G41") (pintype "power_in"))
      (node (ref "U11") (pin "G42") (pinfunction "GND_G42") (pintype "power_in"))
      (node (ref "U11") (pin "G43") (pinfunction "GND_G43") (pintype "power_in"))
      (node (ref "U11") (pin "G44") (pinfunction "GND_G44") (pintype "power_in"))
      (node (ref "U11") (pin "G45") (pinfunction "GND_G45") (pintype "power_in"))
      (node (ref "U11") (pin "G46") (pinfunction "GND_G46") (pintype "power_in"))
      (node (ref "U11") (pin "G47") (pinfunction "GND_G47") (pintype "power_in"))
      (node (ref "U11") (pin "G48") (pinfunction "GND_G48") (pintype "power_in"))
      (node (ref "U11") (pin "G5") (pinfunction "GND_G5") (pintype "power_in"))
      (node (ref "U11") (pin "G6") (pinfunction "GND_G6") (pintype "power_in"))
      (node (ref "U11") (pin "G7") (pinfunction "GND_G7") (pintype "power_in"))
      (node (ref "U11") (pin "G8") (pinfunction "GND_G8") (pintype "power_in"))
      (node (ref "U11") (pin "G9") (pinfunction "GND_G9") (pintype "power_in"))
      (node (ref "U11") (pin "P1") (pinfunction "GND_P1") (pintype "power_in"))
      (node (ref "U11") (pin "P12") (pinfunction "GND_P12") (pintype "power_in"))
      (node (ref "U11") (pin "P14") (pinfunction "GND_P14") (pintype "power_in"))
      (node (ref "U11") (pin "P3") (pinfunction "GND_P3") (pintype "power_in"))
      (node (ref "U11") (pin "P32") (pinfunction "GND_P32") (pintype "power_in"))
      (node (ref "U11") (pin "P37") (pinfunction "GND_P37") (pintype "power_in"))
      (node (ref "U11") (pin "P41") (pinfunction "GND_P41") (pintype "power_in"))
      (node (ref "U11") (pin "P48") (pinfunction "GND_P48") (pintype "power_in"))
      (node (ref "U13") (pin "5") (pinfunction "RES_5") (pintype "bidirectional"))
      (node (ref "U13") (pin "6") (pinfunction "GND_6") (pintype "bidirectional"))
      (node (ref "U13") (pin "7") (pinfunction "GND_7") (pintype "bidirectional"))
      (node (ref "U13") (pin "8") (pinfunction "GND_8") (pintype "bidirectional"))
      (node (ref "U2") (pin "2") (pinfunction "GND_2") (pintype "input"))
      (node (ref "U4") (pin "2") (pinfunction "GND_2") (pintype "input"))
      (node (ref "U5") (pin "1") (pinfunction "GND_1") (pintype "bidirectional"))
      (node (ref "U5") (pin "15") (pinfunction "GND_15") (pintype "bidirectional"))
      (node (ref "U5") (pin "38") (pinfunction "GND_38") (pintype "bidirectional"))
      (node (ref "U5") (pin "GND1") (pinfunction "GND_GND1") (pintype "bidirectional"))
      (node (ref "U5") (pin "GNDT1") (pinfunction "GND_GNDT1") (pintype "bidirectional"))
      (node (ref "U5") (pin "GNDT2") (pinfunction "GND_GNDT2") (pintype "bidirectional"))
      (node (ref "U5") (pin "GNDT3") (pinfunction "GND_GNDT3") (pintype "bidirectional"))
      (node (ref "U5") (pin "GNDT4") (pinfunction "GND_GNDT4") (pintype "bidirectional"))
      (node (ref "U5") (pin "GNDT5") (pinfunction "GND_GNDT5") (pintype "bidirectional"))
      (node (ref "U5") (pin "GNDT6") (pinfunction "GND_GNDT6") (pintype "bidirectional"))
      (node (ref "U5") (pin "GNDT7") (pinfunction "GND_GNDT7") (pintype "bidirectional"))
      (node (ref "U5") (pin "GNDT8") (pinfunction "GND_GNDT8") (pintype "bidirectional"))
      (node (ref "U6") (pin "1") (pinfunction "GND_1") (pintype "bidirectional"))
      (node (ref "U7") (pin "1") (pinfunction "CTG_1") (pintype "input"))
      (node (ref "U7") (pin "4") (pinfunction "GND_4") (pintype "bidirectional"))
      (node (ref "U7") (pin "6") (pinfunction "QSTRT_6") (pintype "bidirectional"))
      (node (ref "U7") (pin "9") (pinfunction "GND_9") (pintype "bidirectional"))
      (node (ref "U8") (pin "P3") (pinfunction "GND_P3") (pintype "power_in"))
      (node (ref "U9") (pin "P3") (pinfunction "GND_P3") (pintype "power_in"))
    )
    (net (code "40") (name "Net-(C1-Pad1)") (class "Default")
      (node (ref "C1") (pin "1") (pinfunction "1_1") (pintype "passive"))
      (node (ref "FB1") (pin "2") (pinfunction "2_2") (pintype "passive"))
      (node (ref "R14") (pin "1") (pinfunction "1_1") (pintype "passive"))
    )
    (net (code "41") (name "Net-(D2-Pad1)") (class "Default")
      (node (ref "D2") (pin "1") (pinfunction "1_1") (pintype "bidirectional"))
      (node (ref "J3") (pin "A7") (pinfunction "D-_A7") (pintype "bidirectional"))
      (node (ref "J3") (pin "B7") (pinfunction "D-_B7") (pintype "bidirectional"))
    )
    (net (code "42") (name "Net-(D2-Pad3)") (class "Default")
      (node (ref "D2") (pin "3") (pinfunction "3_3") (pintype "bidirectional"))
      (node (ref "J3") (pin "A6") (pinfunction "D+_A6") (pintype "bidirectional"))
      (node (ref "J3") (pin "B6") (pinfunction "D+_B6") (pintype "bidirectional"))
    )
    (net (code "43") (name "Net-(D6-Pad1)") (class "Default")
      (node (ref "D6") (pin "1") (pinfunction "1_1") (pintype "bidirectional"))
      (node (ref "J5") (pin "A7") (pinfunction "D-_A7") (pintype "bidirectional"))
      (node (ref "J5") (pin "B7") (pinfunction "D-_B7") (pintype "bidirectional"))
    )
    (net (code "44") (name "Net-(D6-Pad3)") (class "Default")
      (node (ref "D6") (pin "3") (pinfunction "3_3") (pintype "bidirectional"))
      (node (ref "J5") (pin "A6") (pinfunction "D+_A6") (pintype "bidirectional"))
      (node (ref "J5") (pin "B6") (pinfunction "D+_B6") (pintype "bidirectional"))
    )
    (net (code "45") (name "Net-(D9-PadA)") (class "Default")
      (node (ref "D9") (pin "A") (pinfunction "A_A") (pintype "passive"))
      (node (ref "J3") (pin "VBUS1") (pinfunction "VBUS_VBUS1") (pintype "bidirectional"))
      (node (ref "J3") (pin "VBUS2") (pinfunction "VBUS_VBUS2") (pintype "bidirectional"))
    )
    (net (code "46") (name "Net-(E1-SIGNAL)") (class "Default")
      (node (ref "D10") (pin "1") (pinfunction "1_1") (pintype "bidirectional"))
      (node (ref "E1") (pin "SIG") (pinfunction "SIGNAL_SIG") (pintype "bidirectional"))
      (node (ref "FB1") (pin "1") (pinfunction "1_1") (pintype "passive"))
      (node (ref "U11") (pin "P2") (pinfunction "RF_IN_P2") (pintype "input"))
    )
    (net (code "47") (name "Net-(J3-CC1)") (class "Default")
      (node (ref "J3") (pin "A5") (pinfunction "CC1_A5") (pintype "bidirectional"))
      (node (ref "R38") (pin "2") (pinfunction "2_2") (pintype "passive"))
    )
    (net (code "48") (name "Net-(J3-CC2)") (class "Default")
      (node (ref "J3") (pin "B5") (pinfunction "CC2_B5") (pintype "bidirectional"))
      (node (ref "R37") (pin "2") (pinfunction "2_2") (pintype "passive"))
    )
    (net (code "49") (name "Net-(J5-CC1)") (class "Default")
      (node (ref "J5") (pin "A5") (pinfunction "CC1_A5") (pintype "bidirectional"))
      (node (ref "R17") (pin "2") (pinfunction "2_2") (pintype "passive"))
    )
    (net (code "50") (name "Net-(J5-CC2)") (class "Default")
      (node (ref "J5") (pin "B5") (pinfunction "CC2_B5") (pintype "bidirectional"))
      (node (ref "R16") (pin "2") (pinfunction "2_2") (pintype "passive"))
    )
    (net (code "51") (name "Net-(J5-VBUS-PadVBUS1)") (class "Default")
      (node (ref "J5") (pin "VBUS1") (pinfunction "VBUS_VBUS1") (pintype "bidirectional"))
      (node (ref "J5") (pin "VBUS2") (pinfunction "VBUS_VBUS2") (pintype "bidirectional"))
      (node (ref "MEAS") (pin "1") (pinfunction "1_1") (pintype "passive"))
      (node (ref "MEAS") (pin "3") (pinfunction "1_3") (pintype "passive"))
    )
    (net (code "52") (name "Net-(J8-+)") (class "Default")
      (node (ref "J8") (pin "2") (pinfunction "+_2") (pintype "bidirectional"))
      (node (ref "MEAS1") (pin "1") (pinfunction "1_1") (pintype "passive"))
      (node (ref "MEAS1") (pin "3") (pinfunction "1_3") (pintype "passive"))
    )
    (net (code "53") (name "Net-(Q1A-D)") (class "Default")
      (node (ref "C22") (pin "1") (pinfunction "1_1") (pintype "passive"))
      (node (ref "C23") (pin "2") (pinfunction "2_2") (pintype "passive"))
      (node (ref "Q1") (pin "D1") (pinfunction "D_D1") (pintype "bidirectional"))
      (node (ref "Q1") (pin "G2") (pinfunction "G_G2") (pintype "bidirectional"))
      (node (ref "R26") (pin "1") (pinfunction "1_1") (pintype "passive"))
    )
    (net (code "54") (name "Net-(Q2A-B)") (class "Default")
      (node (ref "Q2") (pin "5") (pinfunction "B_5") (pintype "passive"))
      (node (ref "R23") (pin "2") (pinfunction "2_2") (pintype "passive"))
    )
    (net (code "55") (name "Net-(Q2A-E)") (class "Default")
      (node (ref "Q2") (pin "4") (pinfunction "E_4") (pintype "passive"))
      (node (ref "R29") (pin "1") (pinfunction "1_1") (pintype "passive"))
      (node (ref "U6") (pin "14") (pinfunction "~{RTS}_14") (pintype "bidirectional"))
    )
    (net (code "56") (name "Net-(Q2B-B)") (class "Default")
      (node (ref "Q2") (pin "2") (pinfunction "B_2") (pintype "passive"))
      (node (ref "R29") (pin "2") (pinfunction "2_2") (pintype "passive"))
    )
    (net (code "57") (name "Net-(Q2B-E)") (class "Default")
      (node (ref "Q2") (pin "1") (pinfunction "E_1") (pintype "passive"))
      (node (ref "R23") (pin "1") (pinfunction "1_1") (pintype "passive"))
      (node (ref "U6") (pin "13") (pinfunction "~{DTR}_13") (pintype "bidirectional"))
    )
    (net (code "58") (name "Net-(R2A-1)") (class "Default")
      (node (ref "R2") (pin "P1") (pinfunction "1_P1") (pintype "passive"))
      (node (ref "U11") (pin "P45") (pinfunction "SCL/CLK_P45") (pintype "bidirectional"))
    )
    (net (code "59") (name "Net-(R2B-1)") (class "Default")
      (node (ref "R2") (pin "P2") (pinfunction "1_P2") (pintype "passive"))
      (node (ref "U11") (pin "P44") (pinfunction "SDA/~{CS}_P44") (pintype "bidirectional"))
    )
    (net (code "60") (name "Net-(R2C-1)") (class "Default")
      (node (ref "R2") (pin "P3") (pinfunction "1_P3") (pintype "passive"))
      (node (ref "U11") (pin "P43") (pinfunction "RX/MOSI_P43") (pintype "bidirectional"))
    )
    (net (code "61") (name "Net-(R2D-1)") (class "Default")
      (node (ref "R2") (pin "P4") (pinfunction "1_P4") (pintype "passive"))
      (node (ref "U11") (pin "P42") (pinfunction "TX/MISO_P42") (pintype "bidirectional"))
    )
    (net (code "62") (name "Net-(R3A-1)") (class "Default")
      (node (ref "R3") (pin "P1") (pinfunction "1_P1") (pintype "passive"))
      (node (ref "U11") (pin "P50") (pinfunction "~{SAFEBOOT}_P50") (pintype "input"))
    )
    (net (code "63") (name "Net-(R3B-1)") (class "Default")
      (node (ref "R3") (pin "P2") (pinfunction "1_P2") (pintype "passive"))
      (node (ref "U11") (pin "P49") (pinfunction "~{RESET}_P49") (pintype "bidirectional"))
    )
    (net (code "64") (name "Net-(R3C-1)") (class "Default")
      (node (ref "R3") (pin "P3") (pinfunction "1_P3") (pintype "passive"))
      (node (ref "U11") (pin "P47") (pinfunction "D_SEL_P47") (pintype "bidirectional"))
    )
    (net (code "65") (name "Net-(R3D-1)") (class "Default")
      (node (ref "R3") (pin "P4") (pinfunction "1_P4") (pintype "passive"))
      (node (ref "U11") (pin "P46") (pinfunction "TX_READY_P46") (pintype "bidirectional"))
    )
    (net (code "66") (name "Net-(R4A-1)") (class "Default")
      (node (ref "R4") (pin "P1") (pinfunction "1_P1") (pintype "passive"))
      (node (ref "U11") (pin "P27") (pinfunction "TX2_P27") (pintype "output"))
    )
    (net (code "67") (name "Net-(R4B-1)") (class "Default")
      (node (ref "R4") (pin "P2") (pinfunction "1_P2") (pintype "passive"))
      (node (ref "U11") (pin "P26") (pinfunction "RX2_P26") (pintype "input"))
    )
    (net (code "68") (name "Net-(R4C-1)") (class "Default")
      (node (ref "R4") (pin "P3") (pinfunction "1_P3") (pintype "passive"))
      (node (ref "U11") (pin "P23") (pinfunction "DIR_P23") (pintype "input"))
    )
    (net (code "69") (name "Net-(R4D-1)") (class "Default")
      (node (ref "R4") (pin "P4") (pinfunction "1_P4") (pintype "passive"))
      (node (ref "U11") (pin "P22") (pinfunction "WHEEL_TKS_P22") (pintype "input"))
    )
    (net (code "70") (name "Net-(R9A-1)") (class "Default")
      (node (ref "R9") (pin "P1") (pinfunction "1_P1") (pintype "passive"))
      (node (ref "U11") (pin "P53") (pinfunction "TIMEPULSE_P53") (pintype "output"))
    )
    (net (code "71") (name "Net-(R9B-1)") (class "Default")
      (node (ref "R9") (pin "P2") (pinfunction "1_P2") (pintype "passive"))
      (node (ref "U11") (pin "P51") (pinfunction "EXTINT_P51") (pintype "bidirectional"))
    )
    (net (code "72") (name "Net-(R18-Pad2)") (class "Default")
      (node (ref "R18") (pin "2") (pinfunction "2_2") (pintype "bidirectional"))
      (node (ref "R30") (pin "2") (pinfunction "2_2") (pintype "passive"))
      (node (ref "R5") (pin "2") (pinfunction "2_2") (pintype "passive"))
    )
    (net (code "73") (name "Net-(R25C-2)") (class "Default")
      (node (ref "R25") (pin "P6") (pinfunction "2_P6") (pintype "passive"))
      (node (ref "U11") (pin "P19") (pinfunction "GEO_FENCE_STAT_P19") (pintype "output"))
    )
    (net (code "74") (name "Net-(R25D-2)") (class "Default")
      (node (ref "R25") (pin "P5") (pinfunction "2_P5") (pintype "passive"))
      (node (ref "U11") (pin "P20") (pinfunction "RTK_STAT_P20") (pintype "output"))
    )
    (net (code "75") (name "Net-(U5-IO17)") (class "Default")
      (node (ref "R19") (pin "1") (pinfunction "1_1") (pintype "passive"))
      (node (ref "U5") (pin "28") (pinfunction "IO17_28") (pintype "bidirectional"))
    )
    (net (code "76") (name "Net-(U6-UD+)") (class "Default")
      (node (ref "D2") (pin "4") (pinfunction "4_4") (pintype "bidirectional"))
      (node (ref "U6") (pin "5") (pinfunction "UD+_5") (pintype "bidirectional"))
    )
    (net (code "77") (name "Net-(U6-UD-)") (class "Default")
      (node (ref "D2") (pin "6") (pinfunction "6_6") (pintype "bidirectional"))
      (node (ref "U6") (pin "6") (pinfunction "UD-_6") (pintype "bidirectional"))
    )
    (net (code "78") (name "Net-(U10-PROG)") (class "Default")
      (node (ref "R7") (pin "2") (pinfunction "2_2") (pintype "passive"))
      (node (ref "U10") (pin "6") (pinfunction "PROG_6") (pintype "bidirectional"))
    )
    (net (code "79") (name "Net-(U10-THERM)") (class "Default")
      (node (ref "R5") (pin "1") (pinfunction "1_1") (pintype "passive"))
      (node (ref "U10") (pin "8") (pinfunction "THERM_8") (pintype "bidirectional"))
    )
    (net (code "80") (name "Net-(U11-USB_D+)") (class "Default")
      (node (ref "R27") (pin "2") (pinfunction "2_2") (pintype "passive"))
      (node (ref "U11") (pin "P40") (pinfunction "USB_D+_P40") (pintype "bidirectional"))
    )
    (net (code "81") (name "Net-(U11-USB_D-)") (class "Default")
      (node (ref "R28") (pin "2") (pinfunction "2_2") (pintype "passive"))
      (node (ref "U11") (pin "P39") (pinfunction "USB_D-_P39") (pintype "bidirectional"))
    )
    (net (code "82") (name "Net-(U11-V_RF)") (class "Default")
      (node (ref "R14") (pin "2") (pinfunction "2_2") (pintype "passive"))
      (node (ref "U11") (pin "P7") (pinfunction "V_RF_P7") (pintype "output"))
    )
    (net (code "83") (name "POWER_BTN") (class "Default")
      (node (ref "C23") (pin "1") (pinfunction "1_1") (pintype "passive"))
      (node (ref "D1") (pin "C") (pinfunction "C_C") (pintype "passive"))
      (node (ref "J20") (pin "10") (pinfunction "10_10") (pintype "bidirectional"))
      (node (ref "J20") (pin "9") (pinfunction "9_9") (pintype "bidirectional"))
      (node (ref "J7") (pin "4") (pinfunction "4_4") (pintype "passive"))
      (node (ref "JP1") (pin "2") (pinfunction "2_2") (pintype "passive"))
      (node (ref "R31") (pin "1") (pinfunction "1_1") (pintype "passive"))
    )
    (net (code "84") (name "VOUT") (class "Default")
      (node (ref "C20") (pin "1") (pinfunction "1_1") (pintype "passive"))
      (node (ref "C6") (pin "1") (pinfunction "1_1") (pintype "passive"))
      (node (ref "J11") (pin "4") (pinfunction "4_4") (pintype "passive"))
      (node (ref "J9") (pin "1") (pinfunction "1_1") (pintype "passive"))
      (node (ref "Q1") (pin "D2") (pinfunction "D_D2") (pintype "bidirectional"))
      (node (ref "R22") (pin "2") (pinfunction "2_2") (pintype "passive"))
      (node (ref "U2") (pin "1") (pinfunction "IN_1") (pintype "input"))
      (node (ref "U2") (pin "3") (pinfunction "EN_3") (pintype "input"))
    )
    (net (code "85") (name "V_BATT") (class "Default")
      (node (ref "C15") (pin "1") (pinfunction "1_1") (pintype "passive"))
      (node (ref "C17") (pin "1") (pinfunction "1_1") (pintype "passive"))
      (node (ref "C8") (pin "1") (pinfunction "1_1") (pintype "passive"))
      (node (ref "D7") (pin "A") (pinfunction "A_A") (pintype "passive"))
      (node (ref "J10") (pin "1") (pinfunction "1_1") (pintype "passive"))
      (node (ref "MEAS1") (pin "2") (pinfunction "2_2") (pintype "passive"))
      (node (ref "MEAS1") (pin "4") (pinfunction "2_4") (pintype "passive"))
      (node (ref "U10") (pin "10") (pinfunction "VBAT_10") (pintype "bidirectional"))
      (node (ref "U10") (pin "9") (pinfunction "VBAT_9") (pintype "bidirectional"))
      (node (ref "U4") (pin "1") (pinfunction "IN_1") (pintype "input"))
      (node (ref "U4") (pin "3") (pinfunction "EN_3") (pintype "input"))
      (node (ref "U7") (pin "2") (pinfunction "CELL_2") (pintype "input"))
      (node (ref "U7") (pin "3") (pinfunction "VDD_3") (pintype "bidirectional"))
    )
    (net (code "86") (name "V_BKCP") (class "Default")
      (node (ref "C18") (pin "1") (pinfunction "1_1") (pintype "passive"))
      (node (ref "U11") (pin "P36") (pinfunction "V_BKCP_P36") (pintype "power_in"))
      (node (ref "U4") (pin "5") (pinfunction "OUT_5") (pintype "passive"))
    )
    (net (code "87") (name "V_RAW") (class "Default")
      (node (ref "C22") (pin "2") (pinfunction "2_2") (pintype "passive"))
      (node (ref "C9") (pin "1") (pinfunction "1_1") (pintype "passive"))
      (node (ref "D3") (pin "C") (pinfunction "C_C") (pintype "passive"))
      (node (ref "D7") (pin "C") (pinfunction "C_C") (pintype "passive"))
      (node (ref "Q1") (pin "S2") (pinfunction "S_S2") (pintype "bidirectional"))
      (node (ref "R26") (pin "2") (pinfunction "2_2") (pintype "passive"))
      (node (ref "R31") (pin "2") (pinfunction "2_2") (pintype "passive"))
      (node (ref "U10") (pin "1") (pinfunction "VDD_1") (pintype "bidirectional"))
      (node (ref "U10") (pin "2") (pinfunction "VDD_2") (pintype "bidirectional"))
    )
    (net (code "88") (name "V_USB") (class "Default")
      (node (ref "D2") (pin "5") (pinfunction "5_5") (pintype "power_in"))
      (node (ref "D3") (pin "A") (pinfunction "A_A") (pintype "passive"))
      (node (ref "D6") (pin "5") (pinfunction "5_5") (pintype "power_in"))
      (node (ref "D9") (pin "C") (pinfunction "C_C") (pintype "passive"))
      (node (ref "J20") (pin "1") (pinfunction "1_1") (pintype "bidirectional"))
      (node (ref "J20") (pin "2") (pinfunction "2_2") (pintype "bidirectional"))
      (node (ref "MEAS") (pin "2") (pinfunction "2_2") (pintype "passive"))
      (node (ref "MEAS") (pin "4") (pinfunction "2_4") (pintype "passive"))
    )
    (net (code "89") (name "ZED-RXI2") (class "Default")
      (node (ref "J11") (pin "2") (pinfunction "2_2") (pintype "passive"))
      (node (ref "J9") (pin "3") (pinfunction "3_3") (pintype "passive"))
      (node (ref "R4") (pin "P7") (pinfunction "2_P7") (pintype "passive"))
    )
    (net (code "90") (name "ZED-TXO2") (class "Default")
      (node (ref "J11") (pin "3") (pinfunction "3_3") (pintype "passive"))
      (node (ref "J9") (pin "2") (pinfunction "2_2") (pintype "passive"))
      (node (ref "R4") (pin "P8") (pinfunction "2_P8") (pintype "passive"))
    )
    (net (code "91") (name "ZED_DIR") (class "Default")
      (node (ref "R4") (pin "P6") (pinfunction "2_P6") (pintype "passive"))
      (node (ref "U9") (pin "P4") (pinfunction "Y_P4") (pintype "output"))
    )
    (net (code "92") (name "ZED_D_SEL") (class "Default")
      (node (ref "J6") (pin "2") (pinfunction "2_2") (pintype "passive"))
      (node (ref "R3") (pin "P6") (pinfunction "2_P6") (pintype "passive"))
    )
    (net (code "93") (name "ZED_EXTINT") (class "Default")
      (node (ref "R9") (pin "P7") (pinfunction "2_P7") (pintype "passive"))
      (node (ref "U1") (pin "5") (pinfunction "Y1_5") (pintype "bidirectional"))
    )
    (net (code "94") (name "ZED_FENCE_STAT") (class "Default")
      (node (ref "J1") (pin "1") (pinfunction "1_1") (pintype "passive"))
      (node (ref "R25") (pin "P3") (pinfunction "1_P3") (pintype "passive"))
    )
    (net (code "95") (name "ZED_PPS_STAT") (class "Default")
      (node (ref "J6") (pin "5") (pinfunction "5_5") (pintype "passive"))
      (node (ref "R9") (pin "P8") (pinfunction "2_P8") (pintype "passive"))
      (node (ref "U1") (pin "14") (pinfunction "X1_14") (pintype "bidirectional"))
    )
    (net (code "96") (name "ZED_RTK_STAT") (class "Default")
      (node (ref "J1") (pin "2") (pinfunction "2_2") (pintype "passive"))
      (node (ref "R25") (pin "P4") (pinfunction "1_P4") (pintype "passive"))
    )
    (net (code "97") (name "ZED_WT") (class "Default")
      (node (ref "R4") (pin "P5") (pinfunction "2_P5") (pintype "passive"))
      (node (ref "U8") (pin "P4") (pinfunction "Y_P4") (pintype "output"))
    )
    (net (code "98") (name "ZED_~{RESET}") (class "Default")
      (node (ref "J6") (pin "3") (pinfunction "3_3") (pintype "passive"))
      (node (ref "R3") (pin "P7") (pinfunction "2_P7") (pintype "passive"))
    )
    (net (code "99") (name "ZED_~{SAFE}") (class "Default")
      (node (ref "J6") (pin "4") (pinfunction "4_4") (pintype "passive"))
      (node (ref "R3") (pin "P8") (pinfunction "2_P8") (pintype "passive"))
    )
    (net (code "100") (name "unconnected-(J8-PAD1-PadNC1)") (class "Default")
      (node (ref "J8") (pin "NC1") (pinfunction "PAD1_NC1") (pintype "bidirectional"))
    )
    (net (code "101") (name "unconnected-(J8-PAD2-PadNC2)") (class "Default")
      (node (ref "J8") (pin "NC2") (pinfunction "PAD2_NC2") (pintype "bidirectional"))
    )
    (net (code "102") (name "unconnected-(J16-DAT1-Pad8)") (class "Default")
      (node (ref "J16") (pin "8") (pinfunction "DAT1_8") (pintype "bidirectional"))
    )
    (net (code "103") (name "unconnected-(J16-DAT2-Pad1)") (class "Default")
      (node (ref "J16") (pin "1") (pinfunction "DAT2_1") (pintype "bidirectional"))
    )
    (net (code "104") (name "unconnected-(J16-DET-Pad9)") (class "Default")
      (node (ref "J16") (pin "9") (pinfunction "DET_9") (pintype "bidirectional"))
    )
    (net (code "105") (name "unconnected-(J20-Pad5)") (class "Default")
      (node (ref "J20") (pin "5") (pinfunction "5_5") (pintype "bidirectional"))
    )
    (net (code "106") (name "unconnected-(J20-Pad6)") (class "Default")
      (node (ref "J20") (pin "6") (pinfunction "6_6") (pintype "bidirectional"))
    )
    (net (code "107") (name "unconnected-(U2-NC-Pad4)") (class "Default")
      (node (ref "U2") (pin "4") (pinfunction "NC_4") (pintype "no_connect"))
    )
    (net (code "108") (name "unconnected-(U4-NC-Pad4)") (class "Default")
      (node (ref "U4") (pin "4") (pinfunction "NC_4") (pintype "no_connect"))
    )
    (net (code "109") (name "unconnected-(U6-R232-Pad15)") (class "Default")
      (node (ref "U6") (pin "15") (pinfunction "R232_15") (pintype "bidirectional"))
    )
    (net (code "110") (name "unconnected-(U6-~{CTS}-Pad9)") (class "Default")
      (node (ref "U6") (pin "9") (pinfunction "~{CTS}_9") (pintype "bidirectional"))
    )
    (net (code "111") (name "unconnected-(U6-~{DCD}-Pad12)") (class "Default")
      (node (ref "U6") (pin "12") (pinfunction "~{DCD}_12") (pintype "bidirectional"))
    )
    (net (code "112") (name "unconnected-(U6-~{DSR}-Pad10)") (class "Default")
      (node (ref "U6") (pin "10") (pinfunction "~{DSR}_10") (pintype "bidirectional"))
    )
    (net (code "113") (name "unconnected-(U6-~{RI}-Pad11)") (class "Default")
      (node (ref "U6") (pin "11") (pinfunction "~{RI}_11") (pintype "bidirectional"))
    )
    (net (code "114") (name "unconnected-(U7-~{ALRT}-Pad5)") (class "Default")
      (node (ref "U7") (pin "5") (pinfunction "~{ALRT}_5") (pintype "bidirectional"))
    )
    (net (code "115") (name "unconnected-(U10-STAT2-Pad4)") (class "Default")
      (node (ref "U10") (pin "4") (pinfunction "STAT2_4") (pintype "bidirectional"))
    )
    (net (code "116") (name "unconnected-(U10-~{PG}-Pad7)") (class "Default")
      (node (ref "U10") (pin "7") (pinfunction "~{PG}_7") (pintype "bidirectional"))
    )
    (net (code "117") (name "unconnected-(U11-ANT_DETECT-PadP4)") (class "Default")
      (node (ref "U11") (pin "P4") (pinfunction "ANT_DETECT_P4") (pintype "input"))
    )
    (net (code "118") (name "unconnected-(U11-ANT_OFF-PadP5)") (class "Default")
      (node (ref "U11") (pin "P5") (pinfunction "ANT_OFF_P5") (pintype "output"))
    )
    (net (code "119") (name "unconnected-(U11-RSVD-PadP8)") (class "Default")
      (node (ref "U11") (pin "P8") (pinfunction "RSVD_P8") (pintype "no_connect"))
    )
    (net (code "120") (name "unconnected-(U11-RSVD-PadP9)") (class "Default")
      (node (ref "U11") (pin "P9") (pinfunction "RSVD_P9") (pintype "no_connect"))
    )
    (net (code "121") (name "unconnected-(U11-RSVD-PadP10)") (class "Default")
      (node (ref "U11") (pin "P10") (pinfunction "RSVD_P10") (pintype "no_connect"))
    )
    (net (code "122") (name "unconnected-(U11-RSVD-PadP11)") (class "Default")
      (node (ref "U11") (pin "P11") (pinfunction "RSVD_P11") (pintype "no_connect"))
    )
    (net (code "123") (name "unconnected-(U11-RSVD-PadP13)") (class "Default")
      (node (ref "U11") (pin "P13") (pinfunction "RSVD_P13") (pintype "no_connect"))
    )
    (net (code "124") (name "unconnected-(U11-RSVD-PadP15)") (class "Default")
      (node (ref "U11") (pin "P15") (pinfunction "RSVD_P15") (pintype "no_connect"))
    )
    (net (code "125") (name "unconnected-(U11-RSVD-PadP16)") (class "Default")
      (node (ref "U11") (pin "P16") (pinfunction "RSVD_P16") (pintype "no_connect"))
    )
    (net (code "126") (name "unconnected-(U11-RSVD-PadP17)") (class "Default")
      (node (ref "U11") (pin "P17") (pinfunction "RSVD_P17") (pintype "no_connect"))
    )
    (net (code "127") (name "unconnected-(U11-RSVD-PadP18)") (class "Default")
      (node (ref "U11") (pin "P18") (pinfunction "RSVD_P18") (pintype "no_connect"))
    )
    (net (code "128") (name "unconnected-(U11-RSVD-PadP21)") (class "Default")
      (node (ref "U11") (pin "P21") (pinfunction "RSVD_P21") (pintype "no_connect"))
    )
    (net (code "129") (name "unconnected-(U11-RSVD-PadP24)") (class "Default")
      (node (ref "U11") (pin "P24") (pinfunction "RSVD_P24") (pintype "no_connect"))
    )
    (net (code "130") (name "unconnected-(U11-RSVD-PadP25)") (class "Default")
      (node (ref "U11") (pin "P25") (pinfunction "RSVD_P25") (pintype "no_connect"))
    )
    (net (code "131") (name "unconnected-(U11-RSVD-PadP28)") (class "Default")
      (node (ref "U11") (pin "P28") (pinfunction "RSVD_P28") (pintype "no_connect"))
    )
    (net (code "132") (name "unconnected-(U11-RSVD-PadP29)") (class "Default")
      (node (ref "U11") (pin "P29") (pinfunction "RSVD_P29") (pintype "no_connect"))
    )
    (net (code "133") (name "unconnected-(U11-RSVD-PadP30)") (class "Default")
      (node (ref "U11") (pin "P30") (pinfunction "RSVD_P30") (pintype "no_connect"))
    )
    (net (code "134") (name "unconnected-(U11-RSVD-PadP31)") (class "Default")
      (node (ref "U11") (pin "P31") (pinfunction "RSVD_P31") (pintype "no_connect"))
    )
    (net (code "135") (name "unconnected-(U11-RSVD-PadP35)") (class "Default")
      (node (ref "U11") (pin "P35") (pinfunction "RSVD_P35") (pintype "no_connect"))
    )
    (net (code "136") (name "unconnected-(U11-RSVD-PadP52)") (class "Default")
      (node (ref "U11") (pin "P52") (pinfunction "RSVD_P52") (pintype "no_connect"))
    )
    (net (code "137") (name "unconnected-(U11-RSVD-PadP54)") (class "Default")
      (node (ref "U11") (pin "P54") (pinfunction "RSVD_P54") (pintype "no_connect"))
    )
    (net (code "138") (name "unconnected-(U11-~{ANT_SHORT}-PadP6)") (class "Default")
      (node (ref "U11") (pin "P6") (pinfunction "~{ANT_SHORT}_P6") (pintype "output"))
    )
    (net (code "139") (name "unconnected-(U13-INT2-Pad11)") (class "Default")
      (node (ref "U13") (pin "11") (pinfunction "INT2_11") (pintype "bidirectional"))
    )
  )
)
